# sensor_sch.net
KiCad netlist of a schematic drawn in Altium Designer
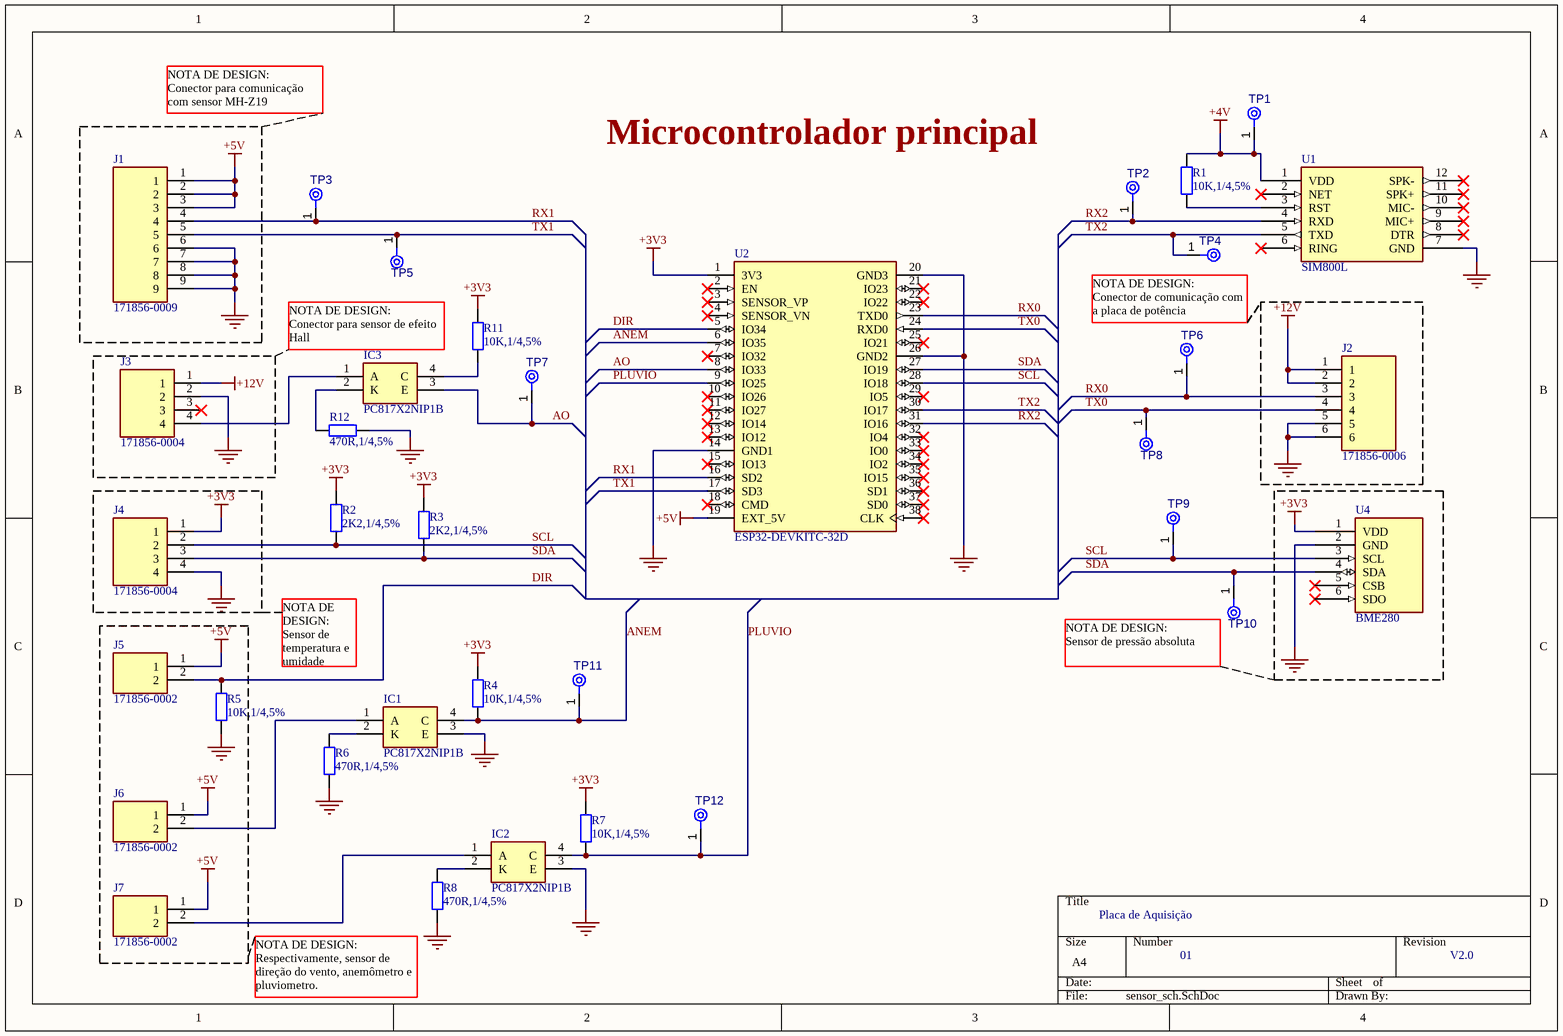
[diagram p0: sensor_sch.SchDoc]

(export (version "E")
  (design (tool "Eeschema 10.0.6"))
  (components
    (comp (ref "IC1")
      (value "PC817X2NIP1B")
      (footprint "sensor_pcblib:SOP254P960X420-4N")
      (description "Transistor Output Optocouplers Photocoupler")
      (fields (field (name "MOUSER PART NUMBER") "852-PC817X2NIP1B") (field (name "MANUFACTURER") "Sharp"))
      (libsource (lib "*") (part "PC817X2NIP1B"))
    )
    (comp (ref "IC2")
      (value "PC817X2NIP1B")
      (footprint "sensor_pcblib:SOP254P960X420-4N")
      (description "Transistor Output Optocouplers Photocoupler")
      (fields (field (name "MOUSER PART NUMBER") "852-PC817X2NIP1B") (field (name "MANUFACTURER") "Sharp"))
      (libsource (lib "*") (part "PC817X2NIP1B"))
    )
    (comp (ref "IC3")
      (value "PC817X2NIP1B")
      (footprint "sensor_pcblib:SOP254P960X420-4N")
      (description "Transistor Output Optocouplers Photocoupler")
      (fields (field (name "MOUSER PART NUMBER") "852-PC817X2NIP1B") (field (name "MANUFACTURER") "Sharp"))
      (libsource (lib "*") (part "PC817X2NIP1B"))
    )
    (comp (ref "J1")
      (value "171856-0009")
      (footprint "sensor_pcblib:SHDR9W99P0X254_1X9_2271X635X818P")
      (description "Headers & Wire Housings KK Hdr Vrt 9 Ckt 2.54mm Pitch Sn")
      (fields (field (name "MOUSER PART NUMBER") "538-171856-0009") (field (name "MANUFACTURER") "Molex"))
      (libsource (lib "*") (part "171856-0009"))
    )
    (comp (ref "J2")
      (value "171856-0006")
      (footprint "sensor_pcblib:HDRV6W99P0X254_1X6_1509X635X1100P")
      (description "Conn Wire to Board HDR 6 POS 2.54mm Solder ST Thru-Hole KK® Bag")
      (fields (field (name "MOUSER PART NUMBER") "538-171856-0006") (field (name "MANUFACTURER") "Molex"))
      (libsource (lib "*") (part "171856-0006"))
    )
    (comp (ref "J3")
      (value "171856-0004")
      (footprint "SHDR4W99P0X254_1X4_1255X635X1124P")
      (description "KK RPC 100 HDR FRLK VERT 04 CKT")
      (fields (field (name "MANUFACTURER") "Molex") (field (name "MANUFACTURER PART NUMBER") "1718560004"))
      (libsource (lib "sensor_lib") (part "171856-0004"))
    )
    (comp (ref "J4")
      (value "171856-0004")
      (footprint "SHDR4W99P0X254_1X4_1255X635X1124P")
      (description "KK RPC 100 HDR FRLK VERT 04 CKT")
      (fields (field (name "MANUFACTURER") "Molex") (field (name "MANUFACTURER PART NUMBER") "1718560004"))
      (libsource (lib "sensor_lib") (part "171856-0004"))
    )
    (comp (ref "J5")
      (value "171856-0002")
      (footprint "sensor_pcblib:SHDR2W99P0X254_1X2_493X635X818P")
      (description "Conn Wire to Board HDR 2 POS 2.54mm Solder ST Thru-Hole KK® Bag")
      (fields (field (name "MOUSER PART NUMBER") "538-171856-0002") (field (name "MANUFACTURER") "Molex"))
      (libsource (lib "sensor_lib") (part "171856-0002"))
    )
    (comp (ref "J6")
      (value "171856-0002")
      (footprint "sensor_pcblib:SHDR2W99P0X254_1X2_493X635X818P")
      (description "Conn Wire to Board HDR 2 POS 2.54mm Solder ST Thru-Hole KK® Bag")
      (fields (field (name "MOUSER PART NUMBER") "538-171856-0002") (field (name "MANUFACTURER") "Molex"))
      (libsource (lib "sensor_lib") (part "171856-0002"))
    )
    (comp (ref "J7")
      (value "171856-0002")
      (footprint "sensor_pcblib:SHDR2W99P0X254_1X2_493X635X818P")
      (description "Conn Wire to Board HDR 2 POS 2.54mm Solder ST Thru-Hole KK® Bag")
      (fields (field (name "MOUSER PART NUMBER") "538-171856-0002") (field (name "MANUFACTURER") "Molex"))
      (libsource (lib "sensor_lib") (part "171856-0002"))
    )
    (comp (ref "R1")
      (value "10K,1/4,5%")
      (footprint "RESC3216X60N")
      (description "VISHAY         CRCW120610K0JNEA             RES, THICK FILM, 10K, 5%, 0.25W, 1206, REEL")
      (fields
        (field (name "MANUFACTURER") "Vishay Dale")
        (field (name "MANUFACTURER PART NUMBER") "CRCW120610K0JNEA")
        (field (name "PUBLISHER") "Altium Limited")
      )
      (libsource (lib "Miscellaneous Devices") (part "Res2"))
    )
    (comp (ref "R2")
      (value "2K2,1/4,5%")
      (footprint "RESC3216X60N")
      (description "VISHAY   CRCW12062K20JNEA   RES, THICK FILM, 2K2, 5%, 0.25W, 1206, REEL")
      (fields
        (field (name "MANUFACTURER") "Vishay Dale")
        (field (name "MANUFACTURER PART NUMBER") "CRCW12062K20JNEA")
        (field (name "PUBLISHER") "Altium Limited")
      )
      (libsource (lib "Miscellaneous Devices") (part "Res2"))
    )
    (comp (ref "R3")
      (value "2K2,1/4,5%")
      (footprint "RESC3216X60N")
      (description "VISHAY   CRCW12062K20JNEA   RES, THICK FILM, 2K2, 5%, 0.25W, 1206, REEL")
      (fields
        (field (name "MANUFACTURER") "Vishay Dale")
        (field (name "MANUFACTURER PART NUMBER") "CRCW12062K20JNEA")
        (field (name "PUBLISHER") "Altium Limited")
      )
      (libsource (lib "Miscellaneous Devices") (part "Res2"))
    )
    (comp (ref "R4")
      (value "10K,1/4,5%")
      (footprint "RESC3216X60N")
      (description "VISHAY         CRCW120610K0JNEA             RES, THICK FILM, 10K, 5%, 0.25W, 1206, REEL")
      (fields
        (field (name "MANUFACTURER") "Vishay Dale")
        (field (name "MANUFACTURER PART NUMBER") "CRCW120610K0JNEA")
        (field (name "PUBLISHER") "Altium Limited")
      )
      (libsource (lib "Miscellaneous Devices") (part "Res2"))
    )
    (comp (ref "R5")
      (value "10K,1/4,5%")
      (footprint "RESC3216X60N")
      (description "VISHAY         CRCW120610K0JNEA             RES, THICK FILM, 10K, 5%, 0.25W, 1206, REEL")
      (fields
        (field (name "MANUFACTURER") "Vishay Dale")
        (field (name "MANUFACTURER PART NUMBER") "CRCW120610K0JNEA")
        (field (name "PUBLISHER") "Altium Limited")
      )
      (libsource (lib "Miscellaneous Devices") (part "Res2"))
    )
    (comp (ref "R6")
      (value "470R,1/4,5%")
      (footprint "RESC3216X60N")
      (description "Thick Film Resistors 1/4watt 470ohms 5%")
      (fields
        (field (name "MANUFACTURER") "Vishay")
        (field (name "MANUFACTURER PART NUMBER") "CRCW1206470RJNEAIF")
        (field (name "PUBLISHER") "Altium Limited")
      )
      (libsource (lib "Miscellaneous Devices") (part "Res2"))
    )
    (comp (ref "R7")
      (value "10K,1/4,5%")
      (footprint "RESC3216X60N")
      (description "VISHAY         CRCW120610K0JNEA             RES, THICK FILM, 10K, 5%, 0.25W, 1206, REEL")
      (fields
        (field (name "MANUFACTURER") "Vishay Dale")
        (field (name "MANUFACTURER PART NUMBER") "CRCW120610K0JNEA")
        (field (name "PUBLISHER") "Altium Limited")
      )
      (libsource (lib "Miscellaneous Devices") (part "Res2"))
    )
    (comp (ref "R8")
      (value "470R,1/4,5%")
      (footprint "RESC3216X60N")
      (description "Thick Film Resistors 1/4watt 470ohms 5%")
      (fields
        (field (name "MANUFACTURER") "Vishay")
        (field (name "MANUFACTURER PART NUMBER") "CRCW1206470RJNEAIF")
        (field (name "PUBLISHER") "Altium Limited")
      )
      (libsource (lib "Miscellaneous Devices") (part "Res2"))
    )
    (comp (ref "R11")
      (value "10K,1/4,5%")
      (footprint "RESC3216X60N")
      (description "VISHAY         CRCW120610K0JNEA             RES, THICK FILM, 10K, 5%, 0.25W, 1206, REEL")
      (fields
        (field (name "MANUFACTURER") "Vishay Dale")
        (field (name "MANUFACTURER PART NUMBER") "CRCW120610K0JNEA")
        (field (name "PUBLISHER") "Altium Limited")
      )
      (libsource (lib "Miscellaneous Devices") (part "Res2"))
    )
    (comp (ref "R12")
      (value "470R,1/4,5%")
      (footprint "RESC3216X60N")
      (description "Thick Film Resistors 1/4watt 470ohms 5%")
      (fields
        (field (name "MANUFACTURER") "Vishay")
        (field (name "MANUFACTURER PART NUMBER") "CRCW1206470RJNEAIF")
        (field (name "PUBLISHER") "Altium Limited")
      )
      (libsource (lib "") (part "Res2_1"))
    )
    (comp (ref "TP1")
      (value "TPAD6R")
      (footprint "TP06R")
      (description "0.6mm round")
      (libsource (lib "PI2") (part "CMP-001-0001-4"))
    )
    (comp (ref "TP2")
      (value "TPAD6R")
      (footprint "TP06R")
      (description "0.6mm round")
      (libsource (lib "PI2") (part "CMP-001-0001-4"))
    )
    (comp (ref "TP3")
      (value "TPAD6R")
      (footprint "TP06R")
      (description "0.6mm round")
      (libsource (lib "PI2") (part "CMP-001-0001-4"))
    )
    (comp (ref "TP4")
      (value "TPAD6R")
      (footprint "TP06R")
      (description "0.6mm round")
      (libsource (lib "PI2") (part "CMP-001-0001-4"))
    )
    (comp (ref "TP5")
      (value "TPAD6R")
      (footprint "TP06R")
      (description "0.6mm round")
      (libsource (lib "PI2") (part "CMP-001-0001-4"))
    )
    (comp (ref "TP6")
      (value "TPAD6R")
      (footprint "TP06R")
      (description "0.6mm round")
      (libsource (lib "PI2") (part "CMP-001-0001-4"))
    )
    (comp (ref "TP7")
      (value "TPAD6R")
      (footprint "TP06R")
      (description "0.6mm round")
      (libsource (lib "PI2") (part "CMP-001-0001-4"))
    )
    (comp (ref "TP8")
      (value "TPAD6R")
      (footprint "TP06R")
      (description "0.6mm round")
      (libsource (lib "PI2") (part "CMP-001-0001-4"))
    )
    (comp (ref "TP9")
      (value "TPAD6R")
      (footprint "TP06R")
      (description "0.6mm round")
      (libsource (lib "PI2") (part "CMP-001-0001-4"))
    )
    (comp (ref "TP10")
      (value "TPAD6R")
      (footprint "TP06R")
      (description "0.6mm round")
      (libsource (lib "PI2") (part "CMP-001-0001-4"))
    )
    (comp (ref "TP11")
      (value "TPAD6R")
      (footprint "TP06R")
      (description "0.6mm round")
      (libsource (lib "PI2") (part "CMP-001-0001-4"))
    )
    (comp (ref "TP12")
      (value "TPAD6R")
      (footprint "TP06R")
      (description "0.6mm round")
      (libsource (lib "PI2") (part "CMP-001-0001-4"))
    )
    (comp (ref "U1") (value "SIM800L") (footprint "SIM800L") (libsource (lib "sensor_lib") (part "SIM800L")))
    (comp (ref "U2")
      (value "ESP32-DEVKITC-32D")
      (footprint "MODULE_ESP32-DEVKITC-32D")
      (description "Espressif Systems ESP32-DevKitC Microcontroller")
      (fields (field (name "MF") "Espressif Systems"))
      (libsource (lib "sensor_lib") (part "ESP32-DEVKITC-32D"))
    )
    (comp (ref "U4")
      (value "BME280")
      (footprint "BME280")
      (description "Digital Pressure Sensor")
      (libsource (lib "sensor_lib") (part "BME280"))
    )
  )
  (nets
    (net (code "1") (name "+3V3") (class "Default")
      (node (ref "J4") (pin "1") (pinfunction "1_1") (pintype "passive"))
      (node (ref "R11") (pin "2") (pinfunction "2_2") (pintype "passive"))
      (node (ref "R2") (pin "2") (pinfunction "2_2") (pintype "passive"))
      (node (ref "R3") (pin "2") (pinfunction "2_2") (pintype "passive"))
      (node (ref "R4") (pin "2") (pinfunction "2_2") (pintype "passive"))
      (node (ref "R7") (pin "2") (pinfunction "2_2") (pintype "passive"))
      (node (ref "U2") (pin "1") (pinfunction "3V3_1") (pintype "power_in"))
      (node (ref "U4") (pin "1") (pinfunction "VDD_1") (pintype "power_in"))
    )
    (net (code "2") (name "+4V") (class "Default")
      (node (ref "R1") (pin "2") (pinfunction "2_2") (pintype "passive"))
      (node (ref "TP1") (pin "1") (pinfunction "TP_1") (pintype "passive"))
      (node (ref "U1") (pin "1") (pinfunction "VDD_1") (pintype "power_in"))
    )
    (net (code "3") (name "+5V") (class "Default")
      (node (ref "J1") (pin "1") (pinfunction "1_1") (pintype "passive"))
      (node (ref "J1") (pin "2") (pinfunction "2_2") (pintype "passive"))
      (node (ref "J1") (pin "3") (pinfunction "3_3") (pintype "passive"))
      (node (ref "J5") (pin "1") (pinfunction "1_1") (pintype "passive"))
      (node (ref "J6") (pin "1") (pinfunction "1_1") (pintype "passive"))
      (node (ref "J7") (pin "1") (pinfunction "1_1") (pintype "passive"))
      (node (ref "U2") (pin "19") (pinfunction "EXT_5V_19") (pintype "power_in"))
    )
    (net (code "4") (name "+12V") (class "Default")
      (node (ref "J2") (pin "1") (pinfunction "1_1") (pintype "passive"))
      (node (ref "J2") (pin "2") (pinfunction "2_2") (pintype "passive"))
      (node (ref "J3") (pin "1") (pinfunction "1_1") (pintype "passive"))
    )
    (net (code "5") (name "/ANEM") (class "Default")
      (node (ref "IC1") (pin "4") (pinfunction "C_4") (pintype "passive"))
      (node (ref "R4") (pin "1") (pinfunction "1_1") (pintype "passive"))
      (node (ref "TP11") (pin "1") (pinfunction "TP_1") (pintype "passive"))
      (node (ref "U2") (pin "6") (pinfunction "IO35_6") (pintype "bidirectional"))
    )
    (net (code "6") (name "/AO") (class "Default")
      (node (ref "IC3") (pin "3") (pinfunction "E_3") (pintype "passive"))
      (node (ref "TP7") (pin "1") (pinfunction "TP_1") (pintype "passive"))
      (node (ref "U2") (pin "8") (pinfunction "IO33_8") (pintype "bidirectional"))
    )
    (net (code "7") (name "/DIR") (class "Default")
      (node (ref "J5") (pin "2") (pinfunction "2_2") (pintype "passive"))
      (node (ref "R5") (pin "2") (pinfunction "2_2") (pintype "passive"))
      (node (ref "U2") (pin "5") (pinfunction "IO34_5") (pintype "bidirectional"))
    )
    (net (code "8") (name "/PLUVIO") (class "Default")
      (node (ref "IC2") (pin "4") (pinfunction "C_4") (pintype "passive"))
      (node (ref "R7") (pin "1") (pinfunction "1_1") (pintype "passive"))
      (node (ref "TP12") (pin "1") (pinfunction "TP_1") (pintype "passive"))
      (node (ref "U2") (pin "9") (pinfunction "IO25_9") (pintype "bidirectional"))
    )
    (net (code "9") (name "/RX0") (class "Default")
      (node (ref "J2") (pin "3") (pinfunction "3_3") (pintype "passive"))
      (node (ref "TP6") (pin "1") (pinfunction "TP_1") (pintype "passive"))
      (node (ref "U2") (pin "23") (pinfunction "TXD0_23") (pintype "output"))
    )
    (net (code "10") (name "/RX1") (class "Default")
      (node (ref "J1") (pin "4") (pinfunction "4_4") (pintype "passive"))
      (node (ref "TP3") (pin "1") (pinfunction "TP_1") (pintype "passive"))
      (node (ref "U2") (pin "16") (pinfunction "SD2_16") (pintype "bidirectional"))
    )
    (net (code "11") (name "/RX2") (class "Default")
      (node (ref "TP2") (pin "1") (pinfunction "TP_1") (pintype "passive"))
      (node (ref "U1") (pin "4") (pinfunction "RXD_4") (pintype "input"))
      (node (ref "U2") (pin "31") (pinfunction "IO16_31") (pintype "bidirectional"))
    )
    (net (code "12") (name "/SCL") (class "Default")
      (node (ref "J4") (pin "2") (pinfunction "2_2") (pintype "passive"))
      (node (ref "R2") (pin "1") (pinfunction "1_1") (pintype "passive"))
      (node (ref "TP9") (pin "1") (pinfunction "TP_1") (pintype "passive"))
      (node (ref "U2") (pin "28") (pinfunction "IO18_28") (pintype "bidirectional"))
      (node (ref "U4") (pin "3") (pinfunction "SCL_3") (pintype "input"))
    )
    (net (code "13") (name "/SDA") (class "Default")
      (node (ref "J4") (pin "3") (pinfunction "3_3") (pintype "passive"))
      (node (ref "R3") (pin "1") (pinfunction "1_1") (pintype "passive"))
      (node (ref "TP10") (pin "1") (pinfunction "TP_1") (pintype "passive"))
      (node (ref "U2") (pin "27") (pinfunction "IO19_27") (pintype "bidirectional"))
      (node (ref "U4") (pin "4") (pinfunction "SDA_4") (pintype "bidirectional"))
    )
    (net (code "14") (name "/TX0") (class "Default")
      (node (ref "J2") (pin "4") (pinfunction "4_4") (pintype "passive"))
      (node (ref "TP8") (pin "1") (pinfunction "TP_1") (pintype "passive"))
      (node (ref "U2") (pin "24") (pinfunction "RXD0_24") (pintype "input"))
    )
    (net (code "15") (name "/TX1") (class "Default")
      (node (ref "J1") (pin "5") (pinfunction "5_5") (pintype "passive"))
      (node (ref "TP5") (pin "1") (pinfunction "TP_1") (pintype "passive"))
      (node (ref "U2") (pin "17") (pinfunction "SD3_17") (pintype "bidirectional"))
    )
    (net (code "16") (name "/TX2") (class "Default")
      (node (ref "TP4") (pin "1") (pinfunction "TP_1") (pintype "passive"))
      (node (ref "U1") (pin "5") (pinfunction "TXD_5") (pintype "output"))
      (node (ref "U2") (pin "30") (pinfunction "IO17_30") (pintype "bidirectional"))
    )
    (net (code "17") (name "GND") (class "Default")
      (node (ref "IC1") (pin "3") (pinfunction "E_3") (pintype "passive"))
      (node (ref "IC2") (pin "3") (pinfunction "E_3") (pintype "passive"))
      (node (ref "J1") (pin "6") (pinfunction "6_6") (pintype "passive"))
      (node (ref "J1") (pin "7") (pinfunction "7_7") (pintype "passive"))
      (node (ref "J1") (pin "8") (pinfunction "8_8") (pintype "passive"))
      (node (ref "J1") (pin "9") (pinfunction "9_9") (pintype "passive"))
      (node (ref "J2") (pin "5") (pinfunction "5_5") (pintype "passive"))
      (node (ref "J2") (pin "6") (pinfunction "6_6") (pintype "passive"))
      (node (ref "J3") (pin "2") (pinfunction "2_2") (pintype "passive"))
      (node (ref "J4") (pin "4") (pinfunction "4_4") (pintype "passive"))
      (node (ref "R12") (pin "1") (pinfunction "1_1") (pintype "passive"))
      (node (ref "R5") (pin "1") (pinfunction "1_1") (pintype "passive"))
      (node (ref "R6") (pin "1") (pinfunction "1_1") (pintype "passive"))
      (node (ref "R8") (pin "1") (pinfunction "1_1") (pintype "passive"))
      (node (ref "U1") (pin "7") (pinfunction "GND_7") (pintype "power_in"))
      (node (ref "U2") (pin "14") (pinfunction "GND1_14") (pintype "power_in"))
      (node (ref "U2") (pin "20") (pinfunction "GND3_20") (pintype "power_in"))
      (node (ref "U2") (pin "26") (pinfunction "GND2_26") (pintype "power_in"))
      (node (ref "U4") (pin "2") (pinfunction "GND_2") (pintype "power_in"))
    )
    (net (code "18") (name "Net-(IC1-A)") (class "Default")
      (node (ref "IC1") (pin "1") (pinfunction "A_1") (pintype "passive"))
      (node (ref "J6") (pin "2") (pinfunction "2_2") (pintype "passive"))
    )
    (net (code "19") (name "Net-(IC1-K)") (class "Default")
      (node (ref "IC1") (pin "2") (pinfunction "K_2") (pintype "passive"))
      (node (ref "R6") (pin "2") (pinfunction "2_2") (pintype "passive"))
    )
    (net (code "20") (name "Net-(IC2-A)") (class "Default")
      (node (ref "IC2") (pin "1") (pinfunction "A_1") (pintype "passive"))
      (node (ref "J7") (pin "2") (pinfunction "2_2") (pintype "passive"))
    )
    (net (code "21") (name "Net-(IC2-K)") (class "Default")
      (node (ref "IC2") (pin "2") (pinfunction "K_2") (pintype "passive"))
      (node (ref "R8") (pin "2") (pinfunction "2_2") (pintype "passive"))
    )
    (net (code "22") (name "Net-(IC3-A)") (class "Default")
      (node (ref "IC3") (pin "1") (pinfunction "A_1") (pintype "passive"))
      (node (ref "J3") (pin "4") (pinfunction "4_4") (pintype "passive"))
    )
    (net (code "23") (name "Net-(IC3-C)") (class "Default")
      (node (ref "IC3") (pin "4") (pinfunction "C_4") (pintype "passive"))
      (node (ref "R11") (pin "1") (pinfunction "1_1") (pintype "passive"))
    )
    (net (code "24") (name "Net-(IC3-K)") (class "Default")
      (node (ref "IC3") (pin "2") (pinfunction "K_2") (pintype "passive"))
      (node (ref "R12") (pin "2") (pinfunction "2_2") (pintype "passive"))
    )
    (net (code "25") (name "Net-(U1-RST)") (class "Default")
      (node (ref "R1") (pin "1") (pinfunction "1_1") (pintype "passive"))
      (node (ref "U1") (pin "3") (pinfunction "RST_3") (pintype "input"))
    )
    (net (code "26") (name "unconnected-(J3-Pad3)") (class "Default")
      (node (ref "J3") (pin "3") (pinfunction "3_3") (pintype "passive+no_connect"))
    )
    (net (code "27") (name "unconnected-(U1-DTR-Pad8)") (class "Default")
      (node (ref "U1") (pin "8") (pinfunction "DTR_8") (pintype "output+no_connect"))
    )
    (net (code "28") (name "unconnected-(U1-MIC+-Pad9)") (class "Default")
      (node (ref "U1") (pin "9") (pinfunction "MIC+_9") (pintype "output+no_connect"))
    )
    (net (code "29") (name "unconnected-(U1-MIC--Pad10)") (class "Default")
      (node (ref "U1") (pin "10") (pinfunction "MIC-_10") (pintype "output+no_connect"))
    )
    (net (code "30") (name "unconnected-(U1-NET-Pad2)") (class "Default")
      (node (ref "U1") (pin "2") (pinfunction "NET_2") (pintype "input+no_connect"))
    )
    (net (code "31") (name "unconnected-(U1-RING-Pad6)") (class "Default")
      (node (ref "U1") (pin "6") (pinfunction "RING_6") (pintype "input+no_connect"))
    )
    (net (code "32") (name "unconnected-(U1-SPK+-Pad11)") (class "Default")
      (node (ref "U1") (pin "11") (pinfunction "SPK+_11") (pintype "output+no_connect"))
    )
    (net (code "33") (name "unconnected-(U1-SPK--Pad12)") (class "Default")
      (node (ref "U1") (pin "12") (pinfunction "SPK-_12") (pintype "output+no_connect"))
    )
    (net (code "34") (name "unconnected-(U2-CLK-Pad38)") (class "Default")
      (node (ref "U2") (pin "38") (pinfunction "CLK_38") (pintype "input+no_connect"))
    )
    (net (code "35") (name "unconnected-(U2-CMD-Pad18)") (class "Default")
      (node (ref "U2") (pin "18") (pinfunction "CMD_18") (pintype "bidirectional+no_connect"))
    )
    (net (code "36") (name "unconnected-(U2-EN-Pad2)") (class "Default")
      (node (ref "U2") (pin "2") (pinfunction "EN_2") (pintype "input+no_connect"))
    )
    (net (code "37") (name "unconnected-(U2-IO0-Pad33)") (class "Default")
      (node (ref "U2") (pin "33") (pinfunction "IO0_33") (pintype "bidirectional+no_connect"))
    )
    (net (code "38") (name "unconnected-(U2-IO2-Pad34)") (class "Default")
      (node (ref "U2") (pin "34") (pinfunction "IO2_34") (pintype "bidirectional+no_connect"))
    )
    (net (code "39") (name "unconnected-(U2-IO4-Pad32)") (class "Default")
      (node (ref "U2") (pin "32") (pinfunction "IO4_32") (pintype "bidirectional+no_connect"))
    )
    (net (code "40") (name "unconnected-(U2-IO5-Pad29)") (class "Default")
      (node (ref "U2") (pin "29") (pinfunction "IO5_29") (pintype "bidirectional+no_connect"))
    )
    (net (code "41") (name "unconnected-(U2-IO12-Pad13)") (class "Default")
      (node (ref "U2") (pin "13") (pinfunction "IO12_13") (pintype "bidirectional+no_connect"))
    )
    (net (code "42") (name "unconnected-(U2-IO13-Pad15)") (class "Default")
      (node (ref "U2") (pin "15") (pinfunction "IO13_15") (pintype "bidirectional+no_connect"))
    )
    (net (code "43") (name "unconnected-(U2-IO14-Pad12)") (class "Default")
      (node (ref "U2") (pin "12") (pinfunction "IO14_12") (pintype "bidirectional+no_connect"))
    )
    (net (code "44") (name "unconnected-(U2-IO15-Pad35)") (class "Default")
      (node (ref "U2") (pin "35") (pinfunction "IO15_35") (pintype "bidirectional+no_connect"))
    )
    (net (code "45") (name "unconnected-(U2-IO21-Pad25)") (class "Default")
      (node (ref "U2") (pin "25") (pinfunction "IO21_25") (pintype "bidirectional+no_connect"))
    )
    (net (code "46") (name "unconnected-(U2-IO22-Pad22)") (class "Default")
      (node (ref "U2") (pin "22") (pinfunction "IO22_22") (pintype "bidirectional+no_connect"))
    )
    (net (code "47") (name "unconnected-(U2-IO23-Pad21)") (class "Default")
      (node (ref "U2") (pin "21") (pinfunction "IO23_21") (pintype "bidirectional+no_connect"))
    )
    (net (code "48") (name "unconnected-(U2-IO26-Pad10)") (class "Default")
      (node (ref "U2") (pin "10") (pinfunction "IO26_10") (pintype "bidirectional+no_connect"))
    )
    (net (code "49") (name "unconnected-(U2-IO27-Pad11)") (class "Default")
      (node (ref "U2") (pin "11") (pinfunction "IO27_11") (pintype "bidirectional+no_connect"))
    )
    (net (code "50") (name "unconnected-(U2-IO32-Pad7)") (class "Default")
      (node (ref "U2") (pin "7") (pinfunction "IO32_7") (pintype "bidirectional+no_connect"))
    )
    (net (code "51") (name "unconnected-(U2-SD0-Pad37)") (class "Default")
      (node (ref "U2") (pin "37") (pinfunction "SD0_37") (pintype "bidirectional+no_connect"))
    )
    (net (code "52") (name "unconnected-(U2-SD1-Pad36)") (class "Default")
      (node (ref "U2") (pin "36") (pinfunction "SD1_36") (pintype "bidirectional+no_connect"))
    )
    (net (code "53") (name "unconnected-(U2-SENSOR_VN-Pad4)") (class "Default")
      (node (ref "U2") (pin "4") (pinfunction "SENSOR_VN_4") (pintype "input+no_connect"))
    )
    (net (code "54") (name "unconnected-(U2-SENSOR_VP-Pad3)") (class "Default")
      (node (ref "U2") (pin "3") (pinfunction "SENSOR_VP_3") (pintype "input+no_connect"))
    )
    (net (code "55") (name "unconnected-(U4-CSB-Pad5)") (class "Default")
      (node (ref "U4") (pin "5") (pinfunction "CSB_5") (pintype "input+no_connect"))
    )
    (net (code "56") (name "unconnected-(U4-SDO-Pad6)") (class "Default")
      (node (ref "U4") (pin "6") (pinfunction "SDO_6") (pintype "input+no_connect"))
    )
  )
)
